# main-board_v1_9.net
KiCad netlist of a schematic drawn in EAGLE
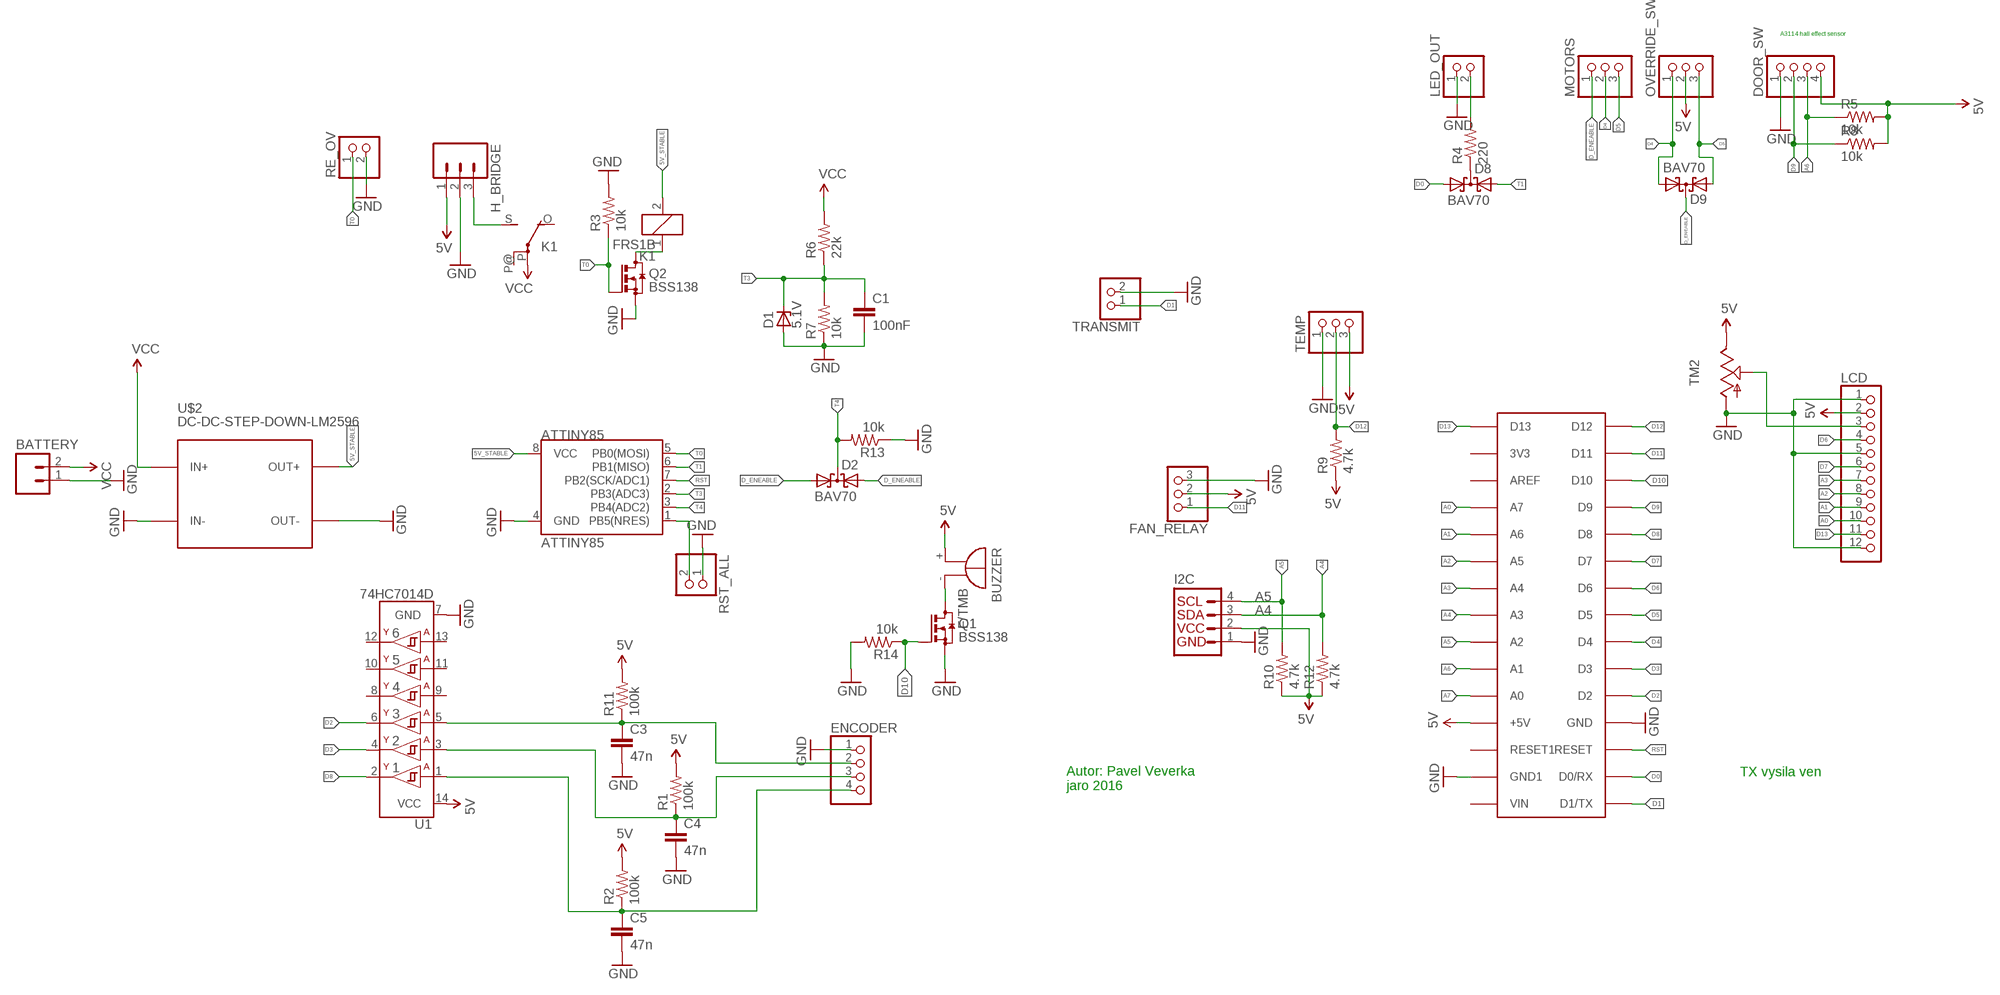
[diagram p0: schematic, sheet 1]

(export (version "E")
  (design (tool "Eeschema 10.0.6"))
  (components
    (comp (ref "ATTINY85")
      (value "ATTINY85")
      (footprint "eagle-import:DIP08")
      (libsource (lib "eagle-import") (part "ATTINY45TINY85-20-DIP"))
    )
    (comp (ref "BATTERY")
      (value "M025MM")
      (footprint "eagle-import:SCREWTERMINAL-5MM-2")
      (libsource (lib "eagle-import") (part "M025MM"))
    )
    (comp (ref "BUZZER")
      (value "F/TMB")
      (footprint "eagle-import:F_TMB")
      (libsource (lib "eagle-import") (part "F/TMB"))
    )
    (comp (ref "C1")
      (value "100nF")
      (footprint "eagle-import:CAP-PTH-5MM")
      (libsource (lib "eagle-import") (part "CAPPTH1"))
    )
    (comp (ref "C3")
      (value "47n")
      (footprint "eagle-import:CAP-PTH-5MM")
      (libsource (lib "eagle-import") (part "CAPPTH1"))
    )
    (comp (ref "C4")
      (value "47n")
      (footprint "eagle-import:CAP-PTH-5MM")
      (libsource (lib "eagle-import") (part "CAPPTH1"))
    )
    (comp (ref "C5")
      (value "47n")
      (footprint "eagle-import:CAP-PTH-5MM")
      (libsource (lib "eagle-import") (part "CAPPTH1"))
    )
    (comp (ref "D1")
      (value "5.1V")
      (footprint "eagle-import:ZDIO-7.5")
      (libsource (lib "eagle-import") (part "ZENER-DIODEZD-7.5"))
    )
    (comp (ref "D2")
      (value "BAV70")
      (footprint "eagle-import:SOT23")
      (libsource (lib "eagle-import") (part "BAS70-05"))
    )
    (comp (ref "D8")
      (value "BAV70")
      (footprint "eagle-import:SOT23")
      (libsource (lib "eagle-import") (part "BAS70-05"))
    )
    (comp (ref "D9")
      (value "BAV70")
      (footprint "eagle-import:SOT23")
      (libsource (lib "eagle-import") (part "BAS70-05"))
    )
    (comp (ref "DOOR_SW")
      (value "PINHD-1X4")
      (footprint "eagle-import:1X04")
      (libsource (lib "eagle-import") (part "PINHD-1X4"))
    )
    (comp (ref "ENCODER")
      (value "PINHD-1X4")
      (footprint "eagle-import:1X04")
      (libsource (lib "eagle-import") (part "PINHD-1X4"))
    )
    (comp (ref "FAN_RELAY")
      (value "PINHD-1X3")
      (footprint "eagle-import:1X03")
      (libsource (lib "eagle-import") (part "PINHD-1X3"))
    )
    (comp (ref "H_BRIDGE")
      (value "M03-SCREW-5MM")
      (footprint "eagle-import:SCREWTERMINAL-5MM-3")
      (libsource (lib "eagle-import") (part "M03-SCREW-5MM"))
    )
    (comp (ref "I2C")
      (value "I2C_STANDARD")
      (footprint "eagle-import:1X04")
      (libsource (lib "eagle-import") (part "I2C_STANDARD"))
    )
    (comp (ref "K1")
      (value "FRS1B")
      (footprint "eagle-import:FRS1B")
      (libsource (lib "eagle-import") (part "FRS1B"))
    )
    (comp (ref "LCD")
      (value "PINHD-1X12")
      (footprint "eagle-import:1X12")
      (libsource (lib "eagle-import") (part "PINHD-1X12"))
    )
    (comp (ref "LED_OUT")
      (value "PINHD-1X2")
      (footprint "eagle-import:1X02")
      (libsource (lib "eagle-import") (part "PINHD-1X2"))
    )
    (comp (ref "MOTORS")
      (value "PINHD-1X3")
      (footprint "eagle-import:1X03")
      (libsource (lib "eagle-import") (part "PINHD-1X3"))
    )
    (comp (ref "NANO")
      (value "NANO")
      (footprint "eagle-import:PDIP-32")
      (libsource (lib "eagle-import") (part "ARDUINONANO"))
    )
    (comp (ref "OVERRIDE_SW")
      (value "PINHD-1X3")
      (footprint "eagle-import:1X03")
      (libsource (lib "eagle-import") (part "PINHD-1X3"))
    )
    (comp (ref "Q1")
      (value "BSS138")
      (footprint "eagle-import:SOT23")
      (libsource (lib "eagle-import") (part "BSS123"))
    )
    (comp (ref "Q2")
      (value "BSS138")
      (footprint "eagle-import:SOT23")
      (libsource (lib "eagle-import") (part "BSS123"))
    )
    (comp (ref "R1")
      (value "100k")
      (footprint "eagle-import:1206")
      (libsource (lib "eagle-import") (part "RESISTOR1206"))
    )
    (comp (ref "R2")
      (value "100k")
      (footprint "eagle-import:1206")
      (libsource (lib "eagle-import") (part "RESISTOR1206"))
    )
    (comp (ref "R3")
      (value "10k")
      (footprint "eagle-import:1206")
      (libsource (lib "eagle-import") (part "RESISTOR1206"))
    )
    (comp (ref "R4")
      (value "220")
      (footprint "eagle-import:1206")
      (libsource (lib "eagle-import") (part "RESISTOR1206"))
    )
    (comp (ref "R5")
      (value "10k")
      (footprint "eagle-import:1206")
      (libsource (lib "eagle-import") (part "RESISTOR1206"))
    )
    (comp (ref "R6")
      (value "22k")
      (footprint "eagle-import:1206")
      (libsource (lib "eagle-import") (part "RESISTOR1206"))
    )
    (comp (ref "R7")
      (value "10k")
      (footprint "eagle-import:1206")
      (libsource (lib "eagle-import") (part "RESISTOR1206"))
    )
    (comp (ref "R8")
      (value "10k")
      (footprint "eagle-import:1206")
      (libsource (lib "eagle-import") (part "RESISTOR1206"))
    )
    (comp (ref "R9")
      (value "4.7k")
      (footprint "eagle-import:1206")
      (libsource (lib "eagle-import") (part "RESISTOR1206"))
    )
    (comp (ref "R10")
      (value "4.7k")
      (footprint "eagle-import:1206")
      (libsource (lib "eagle-import") (part "RESISTOR1206"))
    )
    (comp (ref "R11")
      (value "100k")
      (footprint "eagle-import:1206")
      (libsource (lib "eagle-import") (part "RESISTOR1206"))
    )
    (comp (ref "R12")
      (value "4.7k")
      (footprint "eagle-import:1206")
      (libsource (lib "eagle-import") (part "RESISTOR1206"))
    )
    (comp (ref "R13")
      (value "10k")
      (footprint "eagle-import:1206")
      (libsource (lib "eagle-import") (part "RESISTOR1206"))
    )
    (comp (ref "R14")
      (value "10k")
      (footprint "eagle-import:1206")
      (libsource (lib "eagle-import") (part "RESISTOR1206"))
    )
    (comp (ref "RE_OV")
      (value "PINHD-1X2")
      (footprint "eagle-import:1X02")
      (libsource (lib "eagle-import") (part "PINHD-1X2"))
    )
    (comp (ref "RST_ALL")
      (value "PINHD-1X2")
      (footprint "eagle-import:1X02")
      (libsource (lib "eagle-import") (part "PINHD-1X2"))
    )
    (comp (ref "TEMP")
      (value "PINHD-1X3")
      (footprint "eagle-import:1X03")
      (libsource (lib "eagle-import") (part "PINHD-1X3"))
    )
    (comp (ref "TM2")
      (value "TRIM")
      (footprint "eagle-import:6MM")
      (libsource (lib "eagle-import") (part "TRIM"))
    )
    (comp (ref "TRANSMIT")
      (value "PINHD-1X2")
      (footprint "eagle-import:1X02")
      (libsource (lib "eagle-import") (part "PINHD-1X2"))
    )
    (comp (ref "U$2")
      (value "DC-DC-STEP-DOWN-LM2596")
      (footprint "eagle-import:DC-DC-STEP-DOWN-LM2596")
      (libsource (lib "eagle-import") (part "DC-DC-STEP-DOWN-LM2596"))
    )
    (comp (ref "U1")
      (value "74HC7014D")
      (footprint "eagle-import:SOIC-14")
      (libsource (lib "eagle-import") (part "74HC7014D"))
    )
  )
  (nets
    (net (code "1") (name "5V") (class "Default")
      (node (ref "BUZZER") (pin "+") (pinfunction "+_+") (pintype "passive"))
      (node (ref "DOOR_SW") (pin "4") (pinfunction "4_4") (pintype "passive"))
      (node (ref "FAN_RELAY") (pin "2") (pinfunction "2_2") (pintype "passive"))
      (node (ref "H_BRIDGE") (pin "1") (pinfunction "1_1") (pintype "passive"))
      (node (ref "I2C") (pin "2") (pinfunction "2_2") (pintype "passive"))
      (node (ref "LCD") (pin "2") (pinfunction "2_2") (pintype "passive"))
      (node (ref "NANO") (pin "+5V") (pinfunction "+5V_+5V") (pintype "bidirectional"))
      (node (ref "OVERRIDE_SW") (pin "2") (pinfunction "2_2") (pintype "passive"))
      (node (ref "R1") (pin "2") (pinfunction "2_2") (pintype "passive"))
      (node (ref "R10") (pin "1") (pinfunction "1_1") (pintype "passive"))
      (node (ref "R11") (pin "2") (pinfunction "2_2") (pintype "passive"))
      (node (ref "R12") (pin "1") (pinfunction "1_1") (pintype "passive"))
      (node (ref "R2") (pin "2") (pinfunction "2_2") (pintype "passive"))
      (node (ref "R5") (pin "2") (pinfunction "2_2") (pintype "passive"))
      (node (ref "R8") (pin "2") (pinfunction "2_2") (pintype "passive"))
      (node (ref "R9") (pin "1") (pinfunction "1_1") (pintype "passive"))
      (node (ref "TEMP") (pin "3") (pinfunction "3_3") (pintype "passive"))
      (node (ref "TM2") (pin "E") (pinfunction "E_E") (pintype "passive"))
      (node (ref "U1") (pin "14") (pinfunction "VCC_14") (pintype "power_in"))
    )
    (net (code "2") (name "5V_STABLE") (class "Default")
      (node (ref "ATTINY85") (pin "8") (pinfunction "VCC_8") (pintype "bidirectional"))
      (node (ref "K1") (pin "2") (pinfunction "2_2") (pintype "passive"))
      (node (ref "U$2") (pin "OUT+") (pinfunction "OUT+_OUT+") (pintype "bidirectional"))
    )
    (net (code "3") (name "A0") (class "Default")
      (node (ref "LCD") (pin "10") (pinfunction "10_10") (pintype "passive"))
      (node (ref "NANO") (pin "A7") (pinfunction "A7_A7") (pintype "bidirectional"))
    )
    (net (code "4") (name "A1") (class "Default")
      (node (ref "LCD") (pin "9") (pinfunction "9_9") (pintype "passive"))
      (node (ref "NANO") (pin "A6") (pinfunction "A6_A6") (pintype "bidirectional"))
    )
    (net (code "5") (name "A2") (class "Default")
      (node (ref "LCD") (pin "8") (pinfunction "8_8") (pintype "passive"))
      (node (ref "NANO") (pin "A5") (pinfunction "A5_A5") (pintype "bidirectional"))
    )
    (net (code "6") (name "A3") (class "Default")
      (node (ref "LCD") (pin "7") (pinfunction "7_7") (pintype "passive"))
      (node (ref "NANO") (pin "A4") (pinfunction "A4_A4") (pintype "bidirectional"))
    )
    (net (code "7") (name "A4") (class "Default")
      (node (ref "I2C") (pin "3") (pinfunction "3_3") (pintype "passive"))
      (node (ref "NANO") (pin "A3") (pinfunction "A3_A3") (pintype "bidirectional"))
      (node (ref "R12") (pin "2") (pinfunction "2_2") (pintype "passive"))
    )
    (net (code "8") (name "A5") (class "Default")
      (node (ref "I2C") (pin "4") (pinfunction "4_4") (pintype "passive"))
      (node (ref "NANO") (pin "A2") (pinfunction "A2_A2") (pintype "bidirectional"))
      (node (ref "R10") (pin "2") (pinfunction "2_2") (pintype "passive"))
    )
    (net (code "9") (name "A6") (class "Default")
      (node (ref "DOOR_SW") (pin "3") (pinfunction "3_3") (pintype "passive"))
      (node (ref "NANO") (pin "A1") (pinfunction "A1_A1") (pintype "bidirectional"))
      (node (ref "R5") (pin "1") (pinfunction "1_1") (pintype "passive"))
    )
    (net (code "10") (name "A7") (class "Default")
      (node (ref "NANO") (pin "A0") (pinfunction "A0_A0") (pintype "bidirectional"))
    )
    (net (code "11") (name "D0") (class "Default")
      (node (ref "D8") (pin "1") (pinfunction "A1_1") (pintype "passive"))
      (node (ref "NANO") (pin "D0/RX") (pinfunction "D0/RX_D0/RX") (pintype "bidirectional"))
    )
    (net (code "12") (name "D1") (class "Default")
      (node (ref "NANO") (pin "D1/TX") (pinfunction "D1/TX_D1/TX") (pintype "bidirectional"))
      (node (ref "TRANSMIT") (pin "1") (pinfunction "1_1") (pintype "passive"))
    )
    (net (code "13") (name "D2") (class "Default")
      (node (ref "NANO") (pin "D2") (pinfunction "D2_D2") (pintype "bidirectional"))
      (node (ref "U1") (pin "6") (pinfunction "3Y_6") (pintype "output"))
    )
    (net (code "14") (name "D3") (class "Default")
      (node (ref "NANO") (pin "D3") (pinfunction "D3_D3") (pintype "bidirectional"))
      (node (ref "U1") (pin "4") (pinfunction "2Y_4") (pintype "output"))
    )
    (net (code "15") (name "D4") (class "Default")
      (node (ref "D9") (pin "1") (pinfunction "A1_1") (pintype "passive"))
      (node (ref "MOTORS") (pin "2") (pinfunction "2_2") (pintype "passive"))
      (node (ref "NANO") (pin "D4") (pinfunction "D4_D4") (pintype "bidirectional"))
      (node (ref "OVERRIDE_SW") (pin "1") (pinfunction "1_1") (pintype "passive"))
    )
    (net (code "16") (name "D5") (class "Default")
      (node (ref "D9") (pin "2") (pinfunction "A2_2") (pintype "passive"))
      (node (ref "MOTORS") (pin "3") (pinfunction "3_3") (pintype "passive"))
      (node (ref "NANO") (pin "D5") (pinfunction "D5_D5") (pintype "bidirectional"))
      (node (ref "OVERRIDE_SW") (pin "3") (pinfunction "3_3") (pintype "passive"))
    )
    (net (code "17") (name "D6") (class "Default")
      (node (ref "LCD") (pin "4") (pinfunction "4_4") (pintype "passive"))
      (node (ref "NANO") (pin "D6") (pinfunction "D6_D6") (pintype "bidirectional"))
    )
    (net (code "18") (name "D7") (class "Default")
      (node (ref "LCD") (pin "6") (pinfunction "6_6") (pintype "passive"))
      (node (ref "NANO") (pin "D7") (pinfunction "D7_D7") (pintype "bidirectional"))
    )
    (net (code "19") (name "D8") (class "Default")
      (node (ref "NANO") (pin "D8") (pinfunction "D8_D8") (pintype "bidirectional"))
      (node (ref "U1") (pin "2") (pinfunction "1Y_2") (pintype "output"))
    )
    (net (code "20") (name "D9") (class "Default")
      (node (ref "DOOR_SW") (pin "2") (pinfunction "2_2") (pintype "passive"))
      (node (ref "NANO") (pin "D9") (pinfunction "D9_D9") (pintype "bidirectional"))
      (node (ref "R8") (pin "1") (pinfunction "1_1") (pintype "passive"))
    )
    (net (code "21") (name "D10") (class "Default")
      (node (ref "NANO") (pin "D10") (pinfunction "D10_D10") (pintype "bidirectional"))
      (node (ref "Q1") (pin "1") (pinfunction "G_1") (pintype "passive"))
      (node (ref "R14") (pin "1") (pinfunction "1_1") (pintype "passive"))
    )
    (net (code "22") (name "D11") (class "Default")
      (node (ref "FAN_RELAY") (pin "1") (pinfunction "1_1") (pintype "passive"))
      (node (ref "NANO") (pin "D11") (pinfunction "D11_D11") (pintype "bidirectional"))
    )
    (net (code "23") (name "D12") (class "Default")
      (node (ref "NANO") (pin "D12") (pinfunction "D12_D12") (pintype "bidirectional"))
      (node (ref "R9") (pin "2") (pinfunction "2_2") (pintype "passive"))
      (node (ref "TEMP") (pin "2") (pinfunction "2_2") (pintype "passive"))
    )
    (net (code "24") (name "D13") (class "Default")
      (node (ref "LCD") (pin "11") (pinfunction "11_11") (pintype "passive"))
      (node (ref "NANO") (pin "D13") (pinfunction "D13_D13") (pintype "bidirectional"))
    )
    (net (code "25") (name "D_ENEABLE") (class "Default")
      (node (ref "D2") (pin "2") (pinfunction "A2_2") (pintype "passive"))
      (node (ref "D9") (pin "3") (pinfunction "C_3") (pintype "passive"))
      (node (ref "MOTORS") (pin "1") (pinfunction "1_1") (pintype "passive"))
    )
    (net (code "26") (name "GND") (class "Default")
      (node (ref "ATTINY85") (pin "4") (pinfunction "GND_4") (pintype "bidirectional"))
      (node (ref "BATTERY") (pin "1") (pinfunction "1_1") (pintype "passive"))
      (node (ref "C1") (pin "2") (pinfunction "2_2") (pintype "passive"))
      (node (ref "C3") (pin "2") (pinfunction "2_2") (pintype "passive"))
      (node (ref "C4") (pin "2") (pinfunction "2_2") (pintype "passive"))
      (node (ref "C5") (pin "2") (pinfunction "2_2") (pintype "passive"))
      (node (ref "D1") (pin "A") (pinfunction "A_A") (pintype "passive"))
      (node (ref "DOOR_SW") (pin "1") (pinfunction "1_1") (pintype "passive"))
      (node (ref "ENCODER") (pin "1") (pinfunction "1_1") (pintype "passive"))
      (node (ref "FAN_RELAY") (pin "3") (pinfunction "3_3") (pintype "passive"))
      (node (ref "H_BRIDGE") (pin "2") (pinfunction "2_2") (pintype "passive"))
      (node (ref "I2C") (pin "1") (pinfunction "1_1") (pintype "passive"))
      (node (ref "LCD") (pin "1") (pinfunction "1_1") (pintype "passive"))
      (node (ref "LCD") (pin "12") (pinfunction "12_12") (pintype "passive"))
      (node (ref "LCD") (pin "5") (pinfunction "5_5") (pintype "passive"))
      (node (ref "LED_OUT") (pin "1") (pinfunction "1_1") (pintype "passive"))
      (node (ref "NANO") (pin "GND") (pinfunction "GND_GND") (pintype "bidirectional"))
      (node (ref "NANO") (pin "GND1") (pinfunction "GND1_GND1") (pintype "bidirectional"))
      (node (ref "Q1") (pin "2") (pinfunction "S_2") (pintype "passive"))
      (node (ref "Q2") (pin "2") (pinfunction "S_2") (pintype "passive"))
      (node (ref "R13") (pin "1") (pinfunction "1_1") (pintype "passive"))
      (node (ref "R14") (pin "2") (pinfunction "2_2") (pintype "passive"))
      (node (ref "R3") (pin "2") (pinfunction "2_2") (pintype "passive"))
      (node (ref "R7") (pin "1") (pinfunction "1_1") (pintype "passive"))
      (node (ref "RE_OV") (pin "2") (pinfunction "2_2") (pintype "passive"))
      (node (ref "RST_ALL") (pin "1") (pinfunction "1_1") (pintype "passive"))
      (node (ref "TEMP") (pin "1") (pinfunction "1_1") (pintype "passive"))
      (node (ref "TM2") (pin "A") (pinfunction "A_A") (pintype "passive"))
      (node (ref "TRANSMIT") (pin "2") (pinfunction "2_2") (pintype "passive"))
      (node (ref "U$2") (pin "IN-") (pinfunction "IN-_IN-") (pintype "bidirectional"))
      (node (ref "U$2") (pin "OUT-") (pinfunction "OUT-_OUT-") (pintype "bidirectional"))
      (node (ref "U1") (pin "7") (pinfunction "GND_7") (pintype "power_in"))
    )
    (net (code "27") (name "Net-(ATTINY85-PB5(NRES))") (class "Default")
      (node (ref "ATTINY85") (pin "1") (pinfunction "PB5(NRES)_1") (pintype "bidirectional"))
      (node (ref "RST_ALL") (pin "2") (pinfunction "2_2") (pintype "passive"))
    )
    (net (code "28") (name "Net-(D8-C)") (class "Default")
      (node (ref "D8") (pin "3") (pinfunction "C_3") (pintype "passive"))
      (node (ref "R4") (pin "1") (pinfunction "1_1") (pintype "passive"))
    )
    (net (code "29") (name "Net-(H_BRIDGE-Pad3)") (class "Default")
      (node (ref "H_BRIDGE") (pin "3") (pinfunction "3_3") (pintype "passive"))
      (node (ref "K1") (pin "S") (pinfunction "S_S") (pintype "passive"))
    )
    (net (code "30") (name "Net-(LCD-Pad3)") (class "Default")
      (node (ref "LCD") (pin "3") (pinfunction "3_3") (pintype "passive"))
      (node (ref "TM2") (pin "S") (pinfunction "S_S") (pintype "passive"))
    )
    (net (code "31") (name "Net-(LED_OUT-Pad2)") (class "Default")
      (node (ref "LED_OUT") (pin "2") (pinfunction "2_2") (pintype "passive"))
      (node (ref "R4") (pin "2") (pinfunction "2_2") (pintype "passive"))
    )
    (net (code "32") (name "Net-(Q1-D)") (class "Default")
      (node (ref "BUZZER") (pin "-") (pinfunction "-_-") (pintype "passive"))
      (node (ref "Q1") (pin "3") (pinfunction "D_3") (pintype "passive"))
    )
    (net (code "33") (name "Net-(Q2-D)") (class "Default")
      (node (ref "K1") (pin "1") (pinfunction "1_1") (pintype "passive"))
      (node (ref "Q2") (pin "3") (pinfunction "D_3") (pintype "passive"))
    )
    (net (code "34") (name "Net-(U1-1A)") (class "Default")
      (node (ref "C5") (pin "1") (pinfunction "1_1") (pintype "passive"))
      (node (ref "ENCODER") (pin "4") (pinfunction "4_4") (pintype "passive"))
      (node (ref "R2") (pin "1") (pinfunction "1_1") (pintype "passive"))
      (node (ref "U1") (pin "1") (pinfunction "1A_1") (pintype "input"))
    )
    (net (code "35") (name "Net-(U1-2A)") (class "Default")
      (node (ref "C4") (pin "1") (pinfunction "1_1") (pintype "passive"))
      (node (ref "ENCODER") (pin "3") (pinfunction "3_3") (pintype "passive"))
      (node (ref "R1") (pin "1") (pinfunction "1_1") (pintype "passive"))
      (node (ref "U1") (pin "3") (pinfunction "2A_3") (pintype "input"))
    )
    (net (code "36") (name "Net-(U1-3A)") (class "Default")
      (node (ref "C3") (pin "1") (pinfunction "1_1") (pintype "passive"))
      (node (ref "ENCODER") (pin "2") (pinfunction "2_2") (pintype "passive"))
      (node (ref "R11") (pin "1") (pinfunction "1_1") (pintype "passive"))
      (node (ref "U1") (pin "5") (pinfunction "3A_5") (pintype "input"))
    )
    (net (code "37") (name "RST") (class "Default")
      (node (ref "ATTINY85") (pin "7") (pinfunction "PB2(SCK/ADC1)_7") (pintype "bidirectional"))
      (node (ref "NANO") (pin "RESET") (pinfunction "RESET_RESET") (pintype "bidirectional"))
    )
    (net (code "38") (name "T0") (class "Default")
      (node (ref "ATTINY85") (pin "5") (pinfunction "PB0(MOSI)_5") (pintype "bidirectional"))
      (node (ref "Q2") (pin "1") (pinfunction "G_1") (pintype "passive"))
      (node (ref "R3") (pin "1") (pinfunction "1_1") (pintype "passive"))
      (node (ref "RE_OV") (pin "1") (pinfunction "1_1") (pintype "passive"))
    )
    (net (code "39") (name "T1") (class "Default")
      (node (ref "ATTINY85") (pin "6") (pinfunction "PB1(MISO)_6") (pintype "bidirectional"))
      (node (ref "D8") (pin "2") (pinfunction "A2_2") (pintype "passive"))
    )
    (net (code "40") (name "T3") (class "Default")
      (node (ref "ATTINY85") (pin "2") (pinfunction "PB3(ADC3)_2") (pintype "bidirectional"))
      (node (ref "C1") (pin "1") (pinfunction "1_1") (pintype "passive"))
      (node (ref "D1") (pin "C") (pinfunction "C_C") (pintype "passive"))
      (node (ref "R6") (pin "1") (pinfunction "1_1") (pintype "passive"))
      (node (ref "R7") (pin "2") (pinfunction "2_2") (pintype "passive"))
    )
    (net (code "41") (name "T4") (class "Default")
      (node (ref "ATTINY85") (pin "3") (pinfunction "PB4(ADC2)_3") (pintype "bidirectional"))
      (node (ref "D2") (pin "3") (pinfunction "C_3") (pintype "passive"))
      (node (ref "R13") (pin "2") (pinfunction "2_2") (pintype "passive"))
    )
    (net (code "42") (name "VCC") (class "Default")
      (node (ref "BATTERY") (pin "2") (pinfunction "2_2") (pintype "passive"))
      (node (ref "K1") (pin "P") (pinfunction "P_P") (pintype "passive"))
      (node (ref "R6") (pin "2") (pinfunction "2_2") (pintype "passive"))
      (node (ref "U$2") (pin "IN+") (pinfunction "IN+_IN+") (pintype "bidirectional"))
    )
    (net (code "43") (name "unconnected-(D2-A1-Pad1)") (class "Default")
      (node (ref "D2") (pin "1") (pinfunction "A1_1") (pintype "passive"))
    )
    (net (code "44") (name "unconnected-(K1-PadO)") (class "Default")
      (node (ref "K1") (pin "O") (pinfunction "O_O") (pintype "passive"))
    )
    (net (code "45") (name "unconnected-(K1B-P-PadP@)") (class "Default")
      (node (ref "K1") (pin "P@") (pinfunction "P_P@") (pintype "passive"))
    )
    (net (code "46") (name "unconnected-(NANO-Pad3V3)") (class "Default")
      (node (ref "NANO") (pin "3V3") (pinfunction "3V3_3V3") (pintype "bidirectional"))
    )
    (net (code "47") (name "unconnected-(NANO-PadAREF)") (class "Default")
      (node (ref "NANO") (pin "AREF") (pinfunction "AREF_AREF") (pintype "bidirectional"))
    )
    (net (code "48") (name "unconnected-(NANO-PadRESET1)") (class "Default")
      (node (ref "NANO") (pin "RESET1") (pinfunction "RESET1_RESET1") (pintype "bidirectional"))
    )
    (net (code "49") (name "unconnected-(NANO-PadVIN)") (class "Default")
      (node (ref "NANO") (pin "VIN") (pinfunction "VIN_VIN") (pintype "bidirectional"))
    )
    (net (code "50") (name "unconnected-(U1-4A-Pad9)") (class "Default")
      (node (ref "U1") (pin "9") (pinfunction "4A_9") (pintype "input"))
    )
    (net (code "51") (name "unconnected-(U1-4Y-Pad8)") (class "Default")
      (node (ref "U1") (pin "8") (pinfunction "4Y_8") (pintype "output"))
    )
    (net (code "52") (name "unconnected-(U1-5A-Pad11)") (class "Default")
      (node (ref "U1") (pin "11") (pinfunction "5A_11") (pintype "input"))
    )
    (net (code "53") (name "unconnected-(U1-5Y-Pad10)") (class "Default")
      (node (ref "U1") (pin "10") (pinfunction "5Y_10") (pintype "output"))
    )
    (net (code "54") (name "unconnected-(U1-6A-Pad13)") (class "Default")
      (node (ref "U1") (pin "13") (pinfunction "6A_13") (pintype "input"))
    )
    (net (code "55") (name "unconnected-(U1-6Y-Pad12)") (class "Default")
      (node (ref "U1") (pin "12") (pinfunction "6Y_12") (pintype "output"))
    )
  )
)
